# profi506_avr_kbd.net
KiCad netlist of a schematic drawn in EAGLE
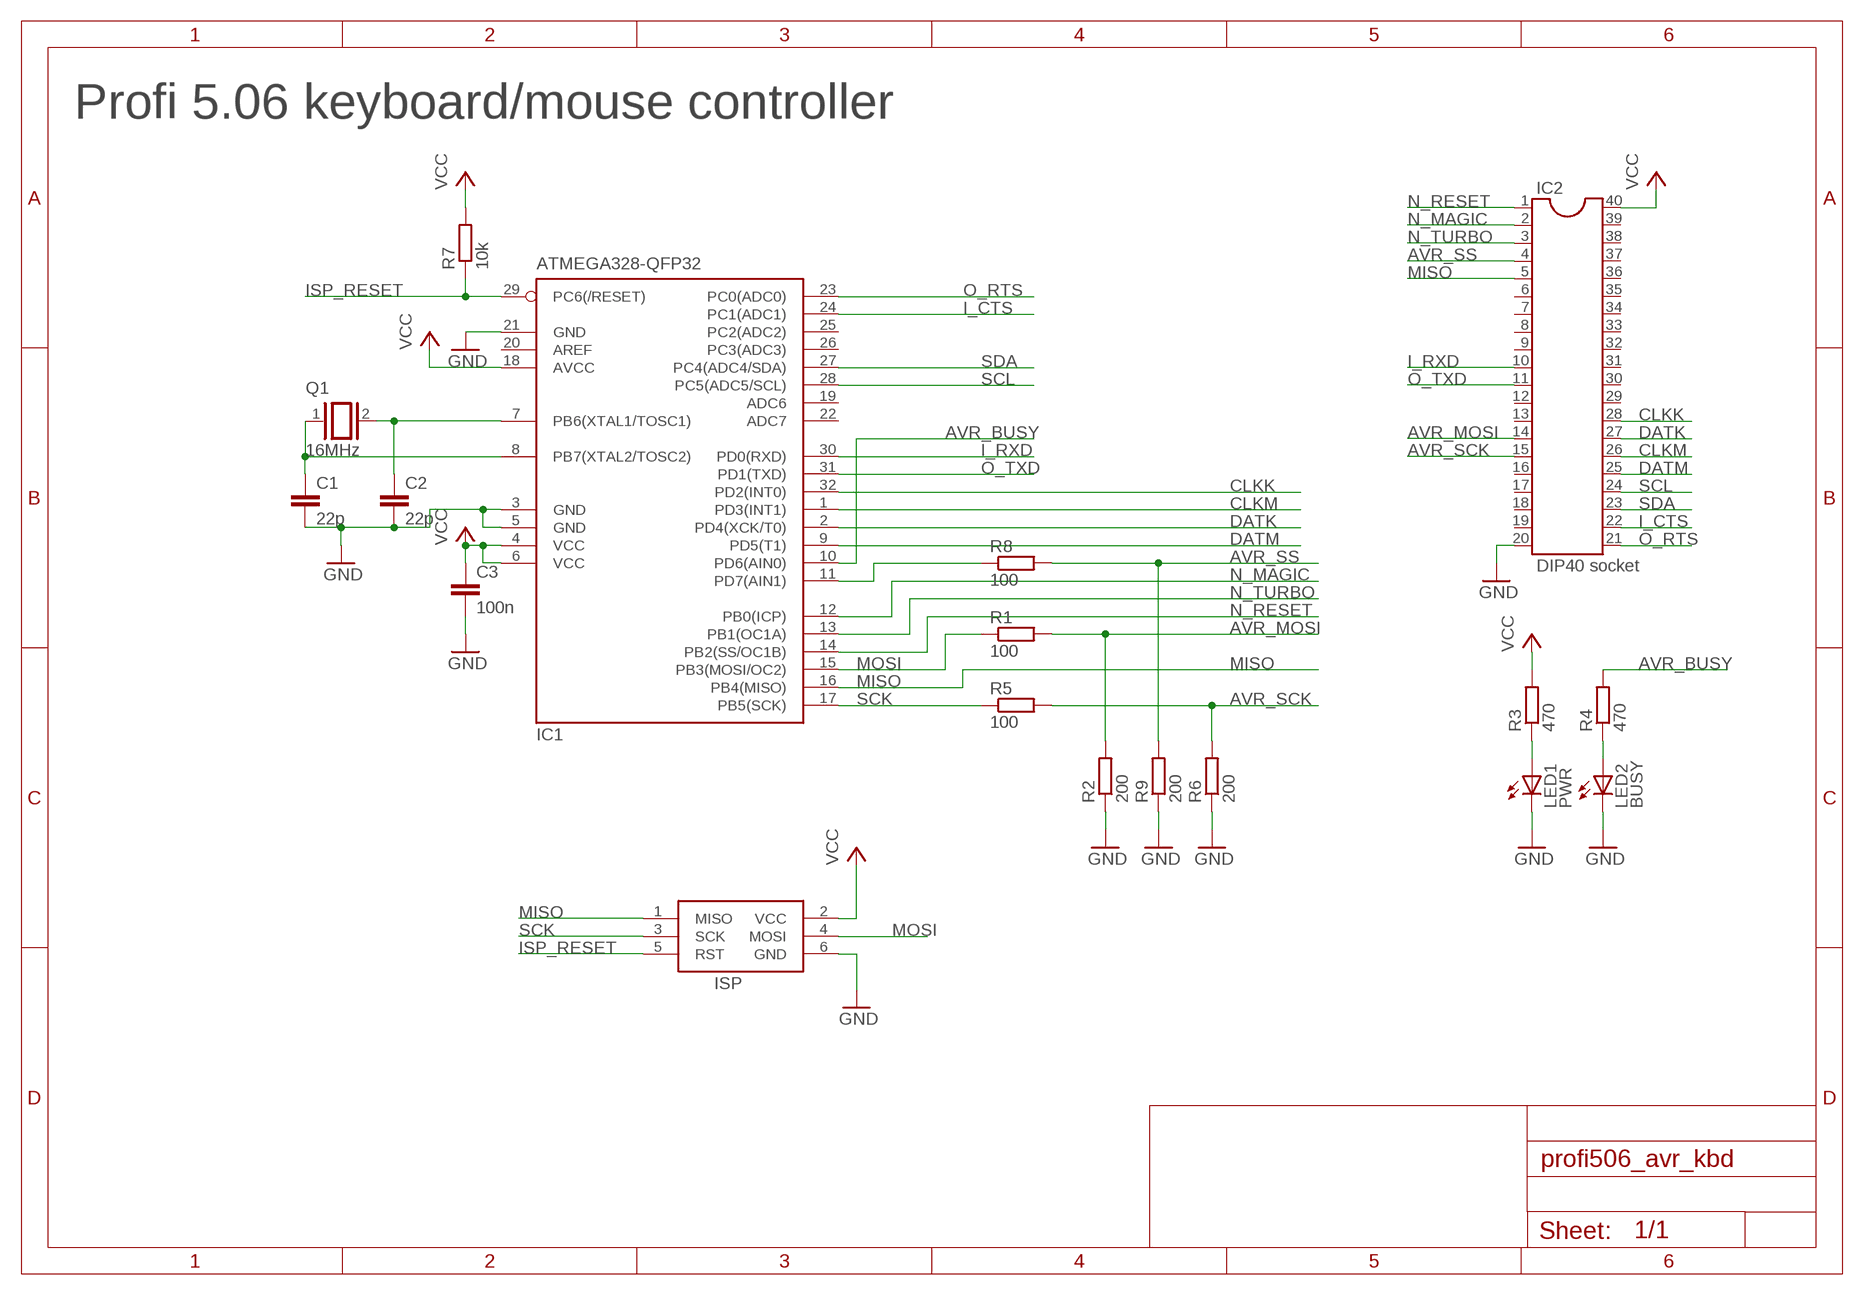
[diagram p0: schematic, sheet 1]

(export (version "E")
  (design (tool "Eeschema 10.0.6"))
  (components
    (comp (ref "C1")
      (value "22p")
      (footprint "eagle-import:C0805")
      (libsource (lib "eagle-import") (part "C-EUC0805"))
    )
    (comp (ref "C2")
      (value "22p")
      (footprint "eagle-import:C0805")
      (libsource (lib "eagle-import") (part "C-EUC0805"))
    )
    (comp (ref "C3")
      (value "100n")
      (footprint "eagle-import:C0805")
      (libsource (lib "eagle-import") (part "C-EUC0805"))
    )
    (comp (ref "IC1")
      (value "ATMEGA328-QFP32")
      (footprint "eagle-import:TQFP32-08")
      (fields (field (name "MPN") "ATMEGA8-16AU"))
      (libsource (lib "eagle-import") (part "MEGA8-AI"))
    )
    (comp (ref "IC2")
      (value "DIP40 socket")
      (footprint "eagle-import:DIL40")
      (libsource (lib "eagle-import") (part "DIL40"))
    )
    (comp (ref "ISP")
      (value "AVRISP-BOX")
      (footprint "eagle-import:AVRISP-BOX")
      (libsource (lib "eagle-import") (part "AVRISP-BOX"))
    )
    (comp (ref "LED1")
      (value "PWR")
      (footprint "eagle-import:CHIPLED_0805")
      (libsource (lib "eagle-import") (part "LEDCHIPLED_0805"))
    )
    (comp (ref "LED2")
      (value "BUSY")
      (footprint "eagle-import:CHIPLED_0805")
      (libsource (lib "eagle-import") (part "LEDCHIPLED_0805"))
    )
    (comp (ref "Q1")
      (value "16MHz")
      (footprint "eagle-import:QS")
      (libsource (lib "eagle-import") (part "XTAL/S"))
    )
    (comp (ref "R1")
      (value "100")
      (footprint "eagle-import:R0805")
      (libsource (lib "eagle-import") (part "R-EU_R0805"))
    )
    (comp (ref "R2")
      (value "200")
      (footprint "eagle-import:R0805")
      (libsource (lib "eagle-import") (part "R-EU_R0805"))
    )
    (comp (ref "R3")
      (value "470")
      (footprint "eagle-import:R0805")
      (libsource (lib "eagle-import") (part "R-EU_R0805"))
    )
    (comp (ref "R4")
      (value "470")
      (footprint "eagle-import:R0805")
      (libsource (lib "eagle-import") (part "R-EU_R0805"))
    )
    (comp (ref "R5")
      (value "100")
      (footprint "eagle-import:R0805")
      (libsource (lib "eagle-import") (part "R-EU_R0805"))
    )
    (comp (ref "R6")
      (value "200")
      (footprint "eagle-import:R0805")
      (libsource (lib "eagle-import") (part "R-EU_R0805"))
    )
    (comp (ref "R7")
      (value "10k")
      (footprint "eagle-import:R0805")
      (libsource (lib "eagle-import") (part "R-EU_R0805"))
    )
    (comp (ref "R8")
      (value "100")
      (footprint "eagle-import:R0805")
      (libsource (lib "eagle-import") (part "R-EU_R0805"))
    )
    (comp (ref "R9")
      (value "200")
      (footprint "eagle-import:R0805")
      (libsource (lib "eagle-import") (part "R-EU_R0805"))
    )
  )
  (nets
    (net (code "1") (name "/AVR_BUSY") (class "Default")
      (node (ref "IC1") (pin "10") (pinfunction "PD6(AIN0)_10") (pintype "bidirectional"))
      (node (ref "R4") (pin "2") (pinfunction "2_2") (pintype "passive"))
    )
    (net (code "2") (name "/AVR_MOSI") (class "Default")
      (node (ref "IC2") (pin "14") (pinfunction "14_14") (pintype "passive"))
      (node (ref "R1") (pin "2") (pinfunction "2_2") (pintype "passive"))
      (node (ref "R2") (pin "2") (pinfunction "2_2") (pintype "passive"))
    )
    (net (code "3") (name "/AVR_SCK") (class "Default")
      (node (ref "IC2") (pin "15") (pinfunction "15_15") (pintype "passive"))
      (node (ref "R5") (pin "2") (pinfunction "2_2") (pintype "passive"))
      (node (ref "R6") (pin "2") (pinfunction "2_2") (pintype "passive"))
    )
    (net (code "4") (name "/AVR_SS") (class "Default")
      (node (ref "IC2") (pin "4") (pinfunction "4_4") (pintype "passive"))
      (node (ref "R8") (pin "2") (pinfunction "2_2") (pintype "passive"))
      (node (ref "R9") (pin "2") (pinfunction "2_2") (pintype "passive"))
    )
    (net (code "5") (name "/CLKK") (class "Default")
      (node (ref "IC1") (pin "32") (pinfunction "PD2(INT0)_32") (pintype "bidirectional"))
      (node (ref "IC2") (pin "28") (pinfunction "28_28") (pintype "passive"))
    )
    (net (code "6") (name "/CLKM") (class "Default")
      (node (ref "IC1") (pin "1") (pinfunction "PD3(INT1)_1") (pintype "bidirectional"))
      (node (ref "IC2") (pin "26") (pinfunction "26_26") (pintype "passive"))
    )
    (net (code "7") (name "/DATK") (class "Default")
      (node (ref "IC1") (pin "2") (pinfunction "PD4(XCK/T0)_2") (pintype "bidirectional"))
      (node (ref "IC2") (pin "27") (pinfunction "27_27") (pintype "passive"))
    )
    (net (code "8") (name "/DATM") (class "Default")
      (node (ref "IC1") (pin "9") (pinfunction "PD5(T1)_9") (pintype "bidirectional"))
      (node (ref "IC2") (pin "25") (pinfunction "25_25") (pintype "passive"))
    )
    (net (code "9") (name "/ISP_RESET") (class "Default")
      (node (ref "IC1") (pin "29") (pinfunction "PC6(/RESET)_29") (pintype "bidirectional"))
      (node (ref "ISP") (pin "5") (pinfunction "RST_5") (pintype "output"))
      (node (ref "R7") (pin "1") (pinfunction "1_1") (pintype "passive"))
    )
    (net (code "10") (name "/I_CTS") (class "Default")
      (node (ref "IC1") (pin "24") (pinfunction "PC1(ADC1)_24") (pintype "bidirectional"))
      (node (ref "IC2") (pin "22") (pinfunction "22_22") (pintype "passive"))
    )
    (net (code "11") (name "/I_RXD") (class "Default")
      (node (ref "IC1") (pin "30") (pinfunction "PD0(RXD)_30") (pintype "bidirectional"))
      (node (ref "IC2") (pin "10") (pinfunction "10_10") (pintype "passive"))
    )
    (net (code "12") (name "/MISO") (class "Default")
      (node (ref "IC1") (pin "16") (pinfunction "PB4(MISO)_16") (pintype "bidirectional"))
      (node (ref "IC2") (pin "5") (pinfunction "5_5") (pintype "passive"))
      (node (ref "ISP") (pin "1") (pinfunction "MISO_1") (pintype "input"))
    )
    (net (code "13") (name "/MOSI") (class "Default")
      (node (ref "IC1") (pin "15") (pinfunction "PB3(MOSI/OC2)_15") (pintype "bidirectional"))
      (node (ref "ISP") (pin "4") (pinfunction "MOSI_4") (pintype "output"))
      (node (ref "R1") (pin "1") (pinfunction "1_1") (pintype "passive"))
    )
    (net (code "14") (name "/N_MAGIC") (class "Default")
      (node (ref "IC1") (pin "12") (pinfunction "PB0(ICP)_12") (pintype "bidirectional"))
      (node (ref "IC2") (pin "2") (pinfunction "2_2") (pintype "passive"))
    )
    (net (code "15") (name "/N_RESET") (class "Default")
      (node (ref "IC1") (pin "14") (pinfunction "PB2(SS/OC1B)_14") (pintype "bidirectional"))
      (node (ref "IC2") (pin "1") (pinfunction "1_1") (pintype "passive"))
    )
    (net (code "16") (name "/N_TURBO") (class "Default")
      (node (ref "IC1") (pin "13") (pinfunction "PB1(OC1A)_13") (pintype "bidirectional"))
      (node (ref "IC2") (pin "3") (pinfunction "3_3") (pintype "passive"))
    )
    (net (code "17") (name "/O_RTS") (class "Default")
      (node (ref "IC1") (pin "23") (pinfunction "PC0(ADC0)_23") (pintype "bidirectional"))
      (node (ref "IC2") (pin "21") (pinfunction "21_21") (pintype "passive"))
    )
    (net (code "18") (name "/O_TXD") (class "Default")
      (node (ref "IC1") (pin "31") (pinfunction "PD1(TXD)_31") (pintype "bidirectional"))
      (node (ref "IC2") (pin "11") (pinfunction "11_11") (pintype "passive"))
    )
    (net (code "19") (name "/SCK") (class "Default")
      (node (ref "IC1") (pin "17") (pinfunction "PB5(SCK)_17") (pintype "bidirectional"))
      (node (ref "ISP") (pin "3") (pinfunction "SCK_3") (pintype "output"))
      (node (ref "R5") (pin "1") (pinfunction "1_1") (pintype "passive"))
    )
    (net (code "20") (name "/SCL") (class "Default")
      (node (ref "IC1") (pin "28") (pinfunction "PC5(ADC5/SCL)_28") (pintype "bidirectional"))
      (node (ref "IC2") (pin "24") (pinfunction "24_24") (pintype "passive"))
    )
    (net (code "21") (name "/SDA") (class "Default")
      (node (ref "IC1") (pin "27") (pinfunction "PC4(ADC4/SDA)_27") (pintype "bidirectional"))
      (node (ref "IC2") (pin "23") (pinfunction "23_23") (pintype "passive"))
    )
    (net (code "22") (name "GND") (class "Default")
      (node (ref "C1") (pin "2") (pinfunction "2_2") (pintype "passive"))
      (node (ref "C2") (pin "2") (pinfunction "2_2") (pintype "passive"))
      (node (ref "C3") (pin "2") (pinfunction "2_2") (pintype "passive"))
      (node (ref "IC1") (pin "21") (pinfunction "GND_21") (pintype "power_in"))
      (node (ref "IC1") (pin "3") (pinfunction "GND_3") (pintype "power_in"))
      (node (ref "IC1") (pin "5") (pinfunction "GND_5") (pintype "power_in"))
      (node (ref "IC2") (pin "20") (pinfunction "20_20") (pintype "passive"))
      (node (ref "ISP") (pin "6") (pinfunction "GND_6") (pintype "power_in"))
      (node (ref "LED1") (pin "C") (pinfunction "C_C") (pintype "passive"))
      (node (ref "LED2") (pin "C") (pinfunction "C_C") (pintype "passive"))
      (node (ref "R2") (pin "1") (pinfunction "1_1") (pintype "passive"))
      (node (ref "R6") (pin "1") (pinfunction "1_1") (pintype "passive"))
      (node (ref "R9") (pin "1") (pinfunction "1_1") (pintype "passive"))
    )
    (net (code "23") (name "Net-(IC1-PB6(XTAL1{slash}TOSC1))") (class "Default")
      (node (ref "C2") (pin "1") (pinfunction "1_1") (pintype "passive"))
      (node (ref "IC1") (pin "7") (pinfunction "PB6(XTAL1/TOSC1)_7") (pintype "bidirectional"))
      (node (ref "Q1") (pin "2") (pinfunction "2_2") (pintype "passive"))
    )
    (net (code "24") (name "Net-(IC1-PB7(XTAL2{slash}TOSC2))") (class "Default")
      (node (ref "C1") (pin "1") (pinfunction "1_1") (pintype "passive"))
      (node (ref "IC1") (pin "8") (pinfunction "PB7(XTAL2/TOSC2)_8") (pintype "bidirectional"))
      (node (ref "Q1") (pin "1") (pinfunction "1_1") (pintype "passive"))
    )
    (net (code "25") (name "Net-(IC1-PD7(AIN1))") (class "Default")
      (node (ref "IC1") (pin "11") (pinfunction "PD7(AIN1)_11") (pintype "bidirectional"))
      (node (ref "R8") (pin "1") (pinfunction "1_1") (pintype "passive"))
    )
    (net (code "26") (name "Net-(LED1-PadA)") (class "Default")
      (node (ref "LED1") (pin "A") (pinfunction "A_A") (pintype "passive"))
      (node (ref "R3") (pin "1") (pinfunction "1_1") (pintype "passive"))
    )
    (net (code "27") (name "Net-(LED2-PadA)") (class "Default")
      (node (ref "LED2") (pin "A") (pinfunction "A_A") (pintype "passive"))
      (node (ref "R4") (pin "1") (pinfunction "1_1") (pintype "passive"))
    )
    (net (code "28") (name "VCC") (class "Default")
      (node (ref "C3") (pin "1") (pinfunction "1_1") (pintype "passive"))
      (node (ref "IC1") (pin "18") (pinfunction "AVCC_18") (pintype "power_in"))
      (node (ref "IC1") (pin "4") (pinfunction "VCC_4") (pintype "power_in"))
      (node (ref "IC1") (pin "6") (pinfunction "VCC_6") (pintype "power_in"))
      (node (ref "IC2") (pin "40") (pinfunction "40_40") (pintype "passive"))
      (node (ref "ISP") (pin "2") (pinfunction "VCC_2") (pintype "power_in"))
      (node (ref "R3") (pin "2") (pinfunction "2_2") (pintype "passive"))
      (node (ref "R7") (pin "2") (pinfunction "2_2") (pintype "passive"))
    )
    (net (code "29") (name "unconnected-(IC1-ADC6-Pad19)") (class "Default")
      (node (ref "IC1") (pin "19") (pinfunction "ADC6_19") (pintype "bidirectional"))
    )
    (net (code "30") (name "unconnected-(IC1-ADC7-Pad22)") (class "Default")
      (node (ref "IC1") (pin "22") (pinfunction "ADC7_22") (pintype "bidirectional"))
    )
    (net (code "31") (name "unconnected-(IC1-AREF-Pad20)") (class "Default")
      (node (ref "IC1") (pin "20") (pinfunction "AREF_20") (pintype "passive"))
    )
    (net (code "32") (name "unconnected-(IC1-PC2(ADC2)-Pad25)") (class "Default")
      (node (ref "IC1") (pin "25") (pinfunction "PC2(ADC2)_25") (pintype "bidirectional"))
    )
    (net (code "33") (name "unconnected-(IC1-PC3(ADC3)-Pad26)") (class "Default")
      (node (ref "IC1") (pin "26") (pinfunction "PC3(ADC3)_26") (pintype "bidirectional"))
    )
    (net (code "34") (name "unconnected-(IC2-Pad6)") (class "Default")
      (node (ref "IC2") (pin "6") (pinfunction "6_6") (pintype "passive"))
    )
    (net (code "35") (name "unconnected-(IC2-Pad7)") (class "Default")
      (node (ref "IC2") (pin "7") (pinfunction "7_7") (pintype "passive"))
    )
    (net (code "36") (name "unconnected-(IC2-Pad8)") (class "Default")
      (node (ref "IC2") (pin "8") (pinfunction "8_8") (pintype "passive"))
    )
    (net (code "37") (name "unconnected-(IC2-Pad9)") (class "Default")
      (node (ref "IC2") (pin "9") (pinfunction "9_9") (pintype "passive"))
    )
    (net (code "38") (name "unconnected-(IC2-Pad12)") (class "Default")
      (node (ref "IC2") (pin "12") (pinfunction "12_12") (pintype "passive"))
    )
    (net (code "39") (name "unconnected-(IC2-Pad13)") (class "Default")
      (node (ref "IC2") (pin "13") (pinfunction "13_13") (pintype "passive"))
    )
    (net (code "40") (name "unconnected-(IC2-Pad16)") (class "Default")
      (node (ref "IC2") (pin "16") (pinfunction "16_16") (pintype "passive"))
    )
    (net (code "41") (name "unconnected-(IC2-Pad17)") (class "Default")
      (node (ref "IC2") (pin "17") (pinfunction "17_17") (pintype "passive"))
    )
    (net (code "42") (name "unconnected-(IC2-Pad18)") (class "Default")
      (node (ref "IC2") (pin "18") (pinfunction "18_18") (pintype "passive"))
    )
    (net (code "43") (name "unconnected-(IC2-Pad19)") (class "Default")
      (node (ref "IC2") (pin "19") (pinfunction "19_19") (pintype "passive"))
    )
    (net (code "44") (name "unconnected-(IC2-Pad29)") (class "Default")
      (node (ref "IC2") (pin "29") (pinfunction "29_29") (pintype "passive"))
    )
    (net (code "45") (name "unconnected-(IC2-Pad30)") (class "Default")
      (node (ref "IC2") (pin "30") (pinfunction "30_30") (pintype "passive"))
    )
    (net (code "46") (name "unconnected-(IC2-Pad31)") (class "Default")
      (node (ref "IC2") (pin "31") (pinfunction "31_31") (pintype "passive"))
    )
    (net (code "47") (name "unconnected-(IC2-Pad32)") (class "Default")
      (node (ref "IC2") (pin "32") (pinfunction "32_32") (pintype "passive"))
    )
    (net (code "48") (name "unconnected-(IC2-Pad33)") (class "Default")
      (node (ref "IC2") (pin "33") (pinfunction "33_33") (pintype "passive"))
    )
    (net (code "49") (name "unconnected-(IC2-Pad34)") (class "Default")
      (node (ref "IC2") (pin "34") (pinfunction "34_34") (pintype "passive"))
    )
    (net (code "50") (name "unconnected-(IC2-Pad35)") (class "Default")
      (node (ref "IC2") (pin "35") (pinfunction "35_35") (pintype "passive"))
    )
    (net (code "51") (name "unconnected-(IC2-Pad36)") (class "Default")
      (node (ref "IC2") (pin "36") (pinfunction "36_36") (pintype "passive"))
    )
    (net (code "52") (name "unconnected-(IC2-Pad37)") (class "Default")
      (node (ref "IC2") (pin "37") (pinfunction "37_37") (pintype "passive"))
    )
    (net (code "53") (name "unconnected-(IC2-Pad38)") (class "Default")
      (node (ref "IC2") (pin "38") (pinfunction "38_38") (pintype "passive"))
    )
    (net (code "54") (name "unconnected-(IC2-Pad39)") (class "Default")
      (node (ref "IC2") (pin "39") (pinfunction "39_39") (pintype "passive"))
    )
  )
)
